# reader.net
KiCad netlist of a schematic drawn in EAGLE
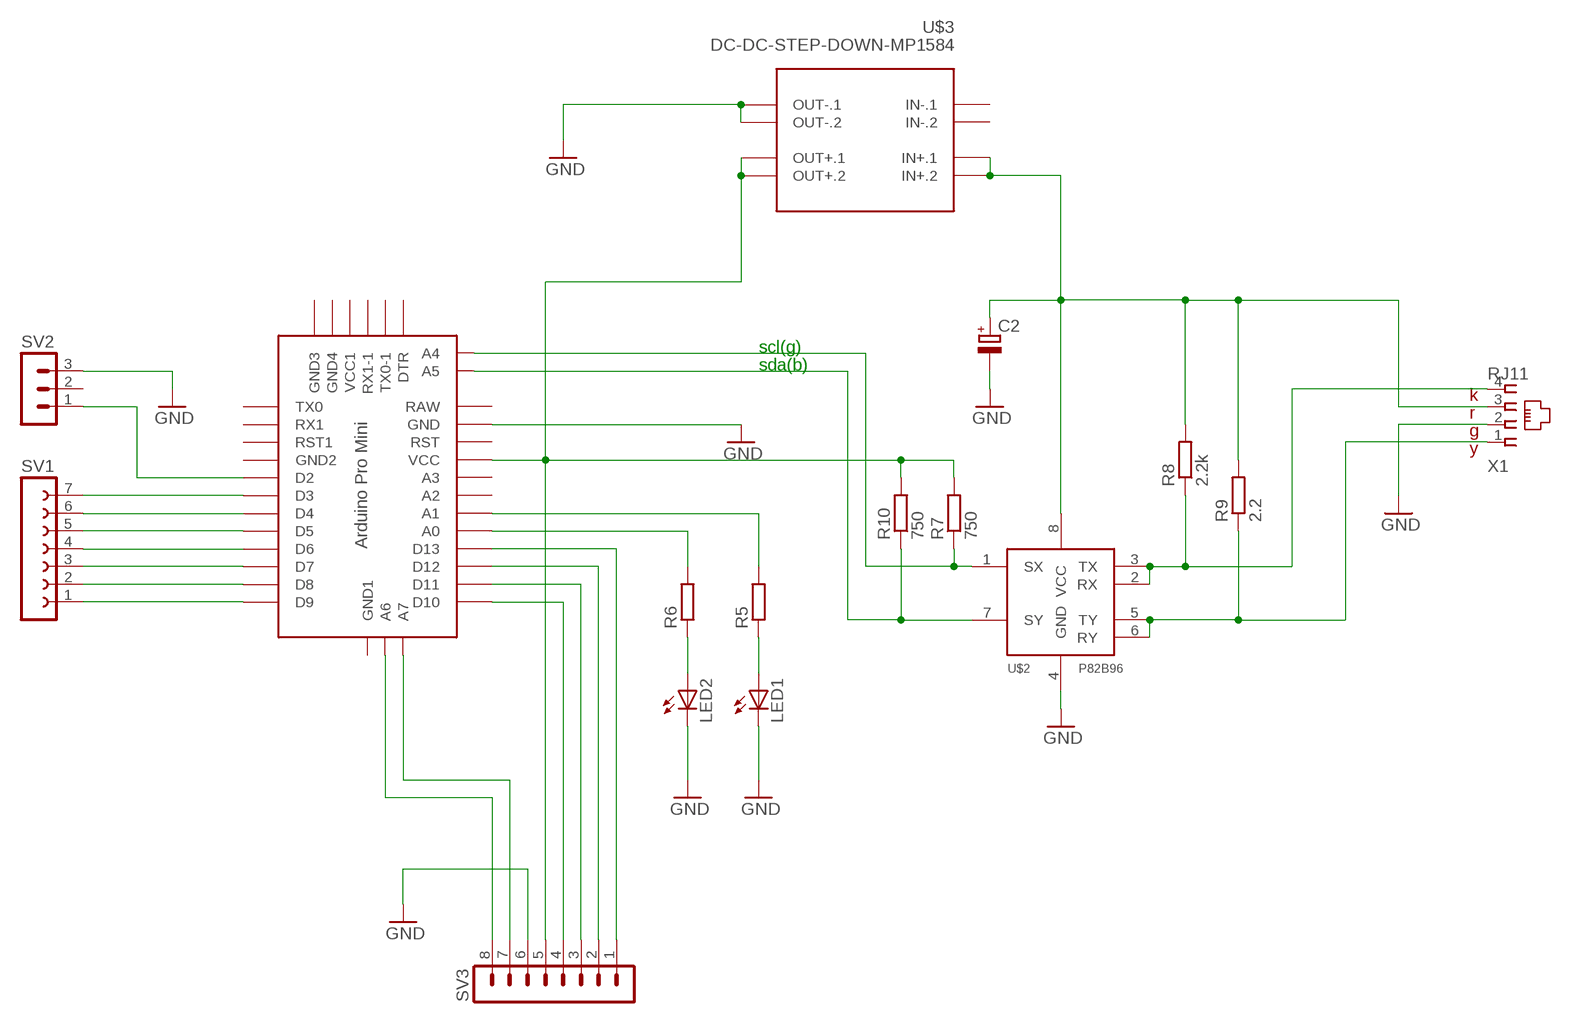
[diagram p0: schematic, sheet 1]

(export (version "E")
  (design (tool "Eeschema 10.0.6"))
  (components
    (comp (ref "C2")
      (value "CPOL-EUE5-6")
      (footprint "eagle-import:E5-6")
      (libsource (lib "eagle-import") (part "CPOL-EUE5-6"))
    )
    (comp (ref "LED1")
      (value "LEDB152")
      (footprint "eagle-import:Q62902-B152")
      (libsource (lib "eagle-import") (part "LEDB152"))
    )
    (comp (ref "LED2")
      (value "LEDB152")
      (footprint "eagle-import:Q62902-B152")
      (libsource (lib "eagle-import") (part "LEDB152"))
    )
    (comp (ref "R5")
      (value "R-EU_M1206")
      (footprint "eagle-import:M1206")
      (libsource (lib "eagle-import") (part "R-EU_M1206"))
    )
    (comp (ref "R6")
      (value "R-EU_M1206")
      (footprint "eagle-import:M1206")
      (libsource (lib "eagle-import") (part "R-EU_M1206"))
    )
    (comp (ref "R7")
      (value "750")
      (footprint "eagle-import:M1206")
      (libsource (lib "eagle-import") (part "R-EU_M1206"))
    )
    (comp (ref "R8")
      (value "2.2k")
      (footprint "eagle-import:M1206")
      (libsource (lib "eagle-import") (part "R-EU_M1206"))
    )
    (comp (ref "R9")
      (value "2.2")
      (footprint "eagle-import:M1206")
      (libsource (lib "eagle-import") (part "R-EU_M1206"))
    )
    (comp (ref "R10")
      (value "750")
      (footprint "eagle-import:M1206")
      (libsource (lib "eagle-import") (part "R-EU_M1206"))
    )
    (comp (ref "SV1")
      (value "FE07-1")
      (footprint "eagle-import:FE07")
      (libsource (lib "eagle-import") (part "FE07-1"))
    )
    (comp (ref "SV2")
      (value "MA03-1")
      (footprint "eagle-import:MA03-1")
      (libsource (lib "eagle-import") (part "MA03-1"))
    )
    (comp (ref "SV3")
      (value "MA08-1")
      (footprint "eagle-import:MA08-1")
      (libsource (lib "eagle-import") (part "MA08-1"))
    )
    (comp (ref "U$1")
      (value "ABK-PRO-MINI")
      (footprint "eagle-import:ABK-PRO-MINI")
      (libsource (lib "eagle-import") (part "ABK-PRO-MINI"))
    )
    (comp (ref "U$2")
      (value "P82B96_")
      (footprint "eagle-import:SOIC8")
      (libsource (lib "eagle-import") (part "P82B96_"))
    )
    (comp (ref "U$3")
      (value "DC-DC-STEP-DOWN-MP1584")
      (footprint "eagle-import:DC-DC-STEP-DOWN-MP1584")
      (libsource (lib "eagle-import") (part "DC-DC-STEP-DOWN-MP1584"))
    )
    (comp (ref "X1")
      (value "RJ11")
      (footprint "eagle-import:RJ11-4P4C")
      (libsource (lib "eagle-import") (part "RJ11"))
    )
  )
  (nets
    (net (code "1") (name "GND") (class "Default")
      (node (ref "C2") (pin "-") (pinfunction "-_-") (pintype "passive"))
      (node (ref "LED1") (pin "K") (pinfunction "C_K") (pintype "passive"))
      (node (ref "LED2") (pin "K") (pinfunction "C_K") (pintype "passive"))
      (node (ref "SV2") (pin "3") (pinfunction "3_3") (pintype "passive"))
      (node (ref "SV3") (pin "6") (pinfunction "6_6") (pintype "passive"))
      (node (ref "U$1") (pin "GND") (pinfunction "GND_GND") (pintype "bidirectional"))
      (node (ref "U$2") (pin "4") (pinfunction "GND_4") (pintype "power_in"))
      (node (ref "U$3") (pin "OUT-.1") (pinfunction "OUT-.1_OUT-.1") (pintype "bidirectional"))
      (node (ref "U$3") (pin "OUT-.2") (pinfunction "OUT-.2_OUT-.2") (pintype "bidirectional"))
      (node (ref "X1") (pin "2") (pinfunction "2_2") (pintype "passive"))
    )
    (net (code "2") (name "Net-(LED1-PadA)") (class "Default")
      (node (ref "LED1") (pin "A") (pinfunction "A_A") (pintype "passive"))
      (node (ref "R5") (pin "1") (pinfunction "1_1") (pintype "passive"))
    )
    (net (code "3") (name "Net-(LED2-PadA)") (class "Default")
      (node (ref "LED2") (pin "A") (pinfunction "A_A") (pintype "passive"))
      (node (ref "R6") (pin "1") (pinfunction "1_1") (pintype "passive"))
    )
    (net (code "4") (name "Net-(R5-Pad2)") (class "Default")
      (node (ref "R5") (pin "2") (pinfunction "2_2") (pintype "passive"))
      (node (ref "U$1") (pin "A1") (pinfunction "A1_A1") (pintype "bidirectional"))
    )
    (net (code "5") (name "Net-(R6-Pad2)") (class "Default")
      (node (ref "R6") (pin "2") (pinfunction "2_2") (pintype "passive"))
      (node (ref "U$1") (pin "A0") (pinfunction "A0_A0") (pintype "bidirectional"))
    )
    (net (code "6") (name "Net-(R10-Pad2)") (class "Default")
      (node (ref "R10") (pin "2") (pinfunction "2_2") (pintype "passive"))
      (node (ref "R7") (pin "2") (pinfunction "2_2") (pintype "passive"))
      (node (ref "SV3") (pin "5") (pinfunction "5_5") (pintype "passive"))
      (node (ref "U$1") (pin "VCC") (pinfunction "VCC_VCC") (pintype "bidirectional"))
      (node (ref "U$3") (pin "OUT+.1") (pinfunction "OUT+.1_OUT+.1") (pintype "bidirectional"))
      (node (ref "U$3") (pin "OUT+.2") (pinfunction "OUT+.2_OUT+.2") (pintype "bidirectional"))
    )
    (net (code "7") (name "Net-(SV1-Pad1)") (class "Default")
      (node (ref "SV1") (pin "1") (pinfunction "1_1") (pintype "passive"))
      (node (ref "U$1") (pin "D9") (pinfunction "D9_D9") (pintype "bidirectional"))
    )
    (net (code "8") (name "Net-(SV1-Pad2)") (class "Default")
      (node (ref "SV1") (pin "2") (pinfunction "2_2") (pintype "passive"))
      (node (ref "U$1") (pin "D8") (pinfunction "D8_D8") (pintype "bidirectional"))
    )
    (net (code "9") (name "Net-(SV1-Pad3)") (class "Default")
      (node (ref "SV1") (pin "3") (pinfunction "3_3") (pintype "passive"))
      (node (ref "U$1") (pin "D7") (pinfunction "D7_D7") (pintype "bidirectional"))
    )
    (net (code "10") (name "Net-(SV1-Pad4)") (class "Default")
      (node (ref "SV1") (pin "4") (pinfunction "4_4") (pintype "passive"))
      (node (ref "U$1") (pin "D6") (pinfunction "D6_D6") (pintype "bidirectional"))
    )
    (net (code "11") (name "Net-(SV1-Pad5)") (class "Default")
      (node (ref "SV1") (pin "5") (pinfunction "5_5") (pintype "passive"))
      (node (ref "U$1") (pin "D5") (pinfunction "D5_D5") (pintype "bidirectional"))
    )
    (net (code "12") (name "Net-(SV1-Pad6)") (class "Default")
      (node (ref "SV1") (pin "6") (pinfunction "6_6") (pintype "passive"))
      (node (ref "U$1") (pin "D4") (pinfunction "D4_D4") (pintype "bidirectional"))
    )
    (net (code "13") (name "Net-(SV1-Pad7)") (class "Default")
      (node (ref "SV1") (pin "7") (pinfunction "7_7") (pintype "passive"))
      (node (ref "U$1") (pin "D3") (pinfunction "D3_D3") (pintype "bidirectional"))
    )
    (net (code "14") (name "Net-(SV2-Pad1)") (class "Default")
      (node (ref "SV2") (pin "1") (pinfunction "1_1") (pintype "passive"))
      (node (ref "U$1") (pin "D2") (pinfunction "D2_D2") (pintype "bidirectional"))
    )
    (net (code "15") (name "Net-(SV3-Pad1)") (class "Default")
      (node (ref "SV3") (pin "1") (pinfunction "1_1") (pintype "passive"))
      (node (ref "U$1") (pin "D13") (pinfunction "D13_D13") (pintype "bidirectional"))
    )
    (net (code "16") (name "Net-(SV3-Pad2)") (class "Default")
      (node (ref "SV3") (pin "2") (pinfunction "2_2") (pintype "passive"))
      (node (ref "U$1") (pin "D12") (pinfunction "D12_D12") (pintype "bidirectional"))
    )
    (net (code "17") (name "Net-(SV3-Pad3)") (class "Default")
      (node (ref "SV3") (pin "3") (pinfunction "3_3") (pintype "passive"))
      (node (ref "U$1") (pin "D11") (pinfunction "D11_D11") (pintype "bidirectional"))
    )
    (net (code "18") (name "Net-(SV3-Pad4)") (class "Default")
      (node (ref "SV3") (pin "4") (pinfunction "4_4") (pintype "passive"))
      (node (ref "U$1") (pin "D10") (pinfunction "D10_D10") (pintype "bidirectional"))
    )
    (net (code "19") (name "Net-(SV3-Pad7)") (class "Default")
      (node (ref "SV3") (pin "7") (pinfunction "7_7") (pintype "passive"))
      (node (ref "U$1") (pin "A7") (pinfunction "A7_A7") (pintype "bidirectional"))
    )
    (net (code "20") (name "Net-(SV3-Pad8)") (class "Default")
      (node (ref "SV3") (pin "8") (pinfunction "8_8") (pintype "passive"))
      (node (ref "U$1") (pin "A6") (pinfunction "A6_A6") (pintype "bidirectional"))
    )
    (net (code "21") (name "Net-(U$2-RX)") (class "Default")
      (node (ref "R8") (pin "1") (pinfunction "1_1") (pintype "passive"))
      (node (ref "U$2") (pin "2") (pinfunction "RX_2") (pintype "bidirectional"))
      (node (ref "U$2") (pin "3") (pinfunction "TX_3") (pintype "bidirectional"))
      (node (ref "X1") (pin "4") (pinfunction "4_4") (pintype "passive"))
    )
    (net (code "22") (name "Net-(U$2-RY)") (class "Default")
      (node (ref "R9") (pin "1") (pinfunction "1_1") (pintype "passive"))
      (node (ref "U$2") (pin "5") (pinfunction "TY_5") (pintype "bidirectional"))
      (node (ref "U$2") (pin "6") (pinfunction "RY_6") (pintype "bidirectional"))
      (node (ref "X1") (pin "1") (pinfunction "1_1") (pintype "passive"))
    )
    (net (code "23") (name "Net-(U$2-SX)") (class "Default")
      (node (ref "R7") (pin "1") (pinfunction "1_1") (pintype "passive"))
      (node (ref "U$1") (pin "A4") (pinfunction "A4_A4") (pintype "bidirectional"))
      (node (ref "U$2") (pin "1") (pinfunction "SX_1") (pintype "input"))
    )
    (net (code "24") (name "Net-(U$2-SY)") (class "Default")
      (node (ref "R10") (pin "1") (pinfunction "1_1") (pintype "passive"))
      (node (ref "U$1") (pin "A5") (pinfunction "A5_A5") (pintype "bidirectional"))
      (node (ref "U$2") (pin "7") (pinfunction "SY_7") (pintype "input"))
    )
    (net (code "25") (name "Net-(U$2-VCC)") (class "Default")
      (node (ref "C2") (pin "+") (pinfunction "+_+") (pintype "passive"))
      (node (ref "R8") (pin "2") (pinfunction "2_2") (pintype "passive"))
      (node (ref "R9") (pin "2") (pinfunction "2_2") (pintype "passive"))
      (node (ref "U$2") (pin "8") (pinfunction "VCC_8") (pintype "power_in"))
      (node (ref "U$3") (pin "IN+.1") (pinfunction "IN+.1_IN+.1") (pintype "bidirectional"))
      (node (ref "U$3") (pin "IN+.2") (pinfunction "IN+.2_IN+.2") (pintype "bidirectional"))
      (node (ref "X1") (pin "3") (pinfunction "3_3") (pintype "passive"))
    )
    (net (code "26") (name "unconnected-(SV2-Pad2)") (class "Default")
      (node (ref "SV2") (pin "2") (pinfunction "2_2") (pintype "passive"))
    )
    (net (code "27") (name "unconnected-(U$1-GND1-PadGND4)") (class "Default")
      (node (ref "U$1") (pin "GND4") (pinfunction "GND1_GND4") (pintype "bidirectional"))
    )
    (net (code "28") (name "unconnected-(U$1-GND2-PadGND1)") (class "Default")
      (node (ref "U$1") (pin "GND1") (pinfunction "GND2_GND1") (pintype "bidirectional"))
    )
    (net (code "29") (name "unconnected-(U$1-GND3-PadGND2)") (class "Default")
      (node (ref "U$1") (pin "GND2") (pinfunction "GND3_GND2") (pintype "bidirectional"))
    )
    (net (code "30") (name "unconnected-(U$1-GND4-PadGND3)") (class "Default")
      (node (ref "U$1") (pin "GND3") (pinfunction "GND4_GND3") (pintype "bidirectional"))
    )
    (net (code "31") (name "unconnected-(U$1-PadA2)") (class "Default")
      (node (ref "U$1") (pin "A2") (pinfunction "A2_A2") (pintype "bidirectional"))
    )
    (net (code "32") (name "unconnected-(U$1-PadA3)") (class "Default")
      (node (ref "U$1") (pin "A3") (pinfunction "A3_A3") (pintype "bidirectional"))
    )
    (net (code "33") (name "unconnected-(U$1-PadDTR)") (class "Default")
      (node (ref "U$1") (pin "DTR") (pinfunction "DTR_DTR") (pintype "bidirectional"))
    )
    (net (code "34") (name "unconnected-(U$1-PadRAW)") (class "Default")
      (node (ref "U$1") (pin "RAW") (pinfunction "RAW_RAW") (pintype "bidirectional"))
    )
    (net (code "35") (name "unconnected-(U$1-PadRST)") (class "Default")
      (node (ref "U$1") (pin "RST") (pinfunction "RST_RST") (pintype "bidirectional"))
    )
    (net (code "36") (name "unconnected-(U$1-PadRST1)") (class "Default")
      (node (ref "U$1") (pin "RST1") (pinfunction "RST1_RST1") (pintype "bidirectional"))
    )
    (net (code "37") (name "unconnected-(U$1-PadRX1)") (class "Default")
      (node (ref "U$1") (pin "RX1") (pinfunction "RX1_RX1") (pintype "bidirectional"))
    )
    (net (code "38") (name "unconnected-(U$1-PadRX1-1)") (class "Default")
      (node (ref "U$1") (pin "RX1-1") (pinfunction "RX1-1_RX1-1") (pintype "bidirectional"))
    )
    (net (code "39") (name "unconnected-(U$1-PadTX0)") (class "Default")
      (node (ref "U$1") (pin "TX0") (pinfunction "TX0_TX0") (pintype "bidirectional"))
    )
    (net (code "40") (name "unconnected-(U$1-PadTX0-1)") (class "Default")
      (node (ref "U$1") (pin "TX0-1") (pinfunction "TX0-1_TX0-1") (pintype "bidirectional"))
    )
    (net (code "41") (name "unconnected-(U$1-PadVCC1)") (class "Default")
      (node (ref "U$1") (pin "VCC1") (pinfunction "VCC1_VCC1") (pintype "bidirectional"))
    )
    (net (code "42") (name "unconnected-(U$3-PadIN-.1)") (class "Default")
      (node (ref "U$3") (pin "IN-.1") (pinfunction "IN-.1_IN-.1") (pintype "bidirectional"))
    )
    (net (code "43") (name "unconnected-(U$3-PadIN-.2)") (class "Default")
      (node (ref "U$3") (pin "IN-.2") (pinfunction "IN-.2_IN-.2") (pintype "bidirectional"))
    )
  )
)
